# Copy_of_SCH_Placa_presentation.net
KiCad netlist of a schematic drawn in Altium Designer
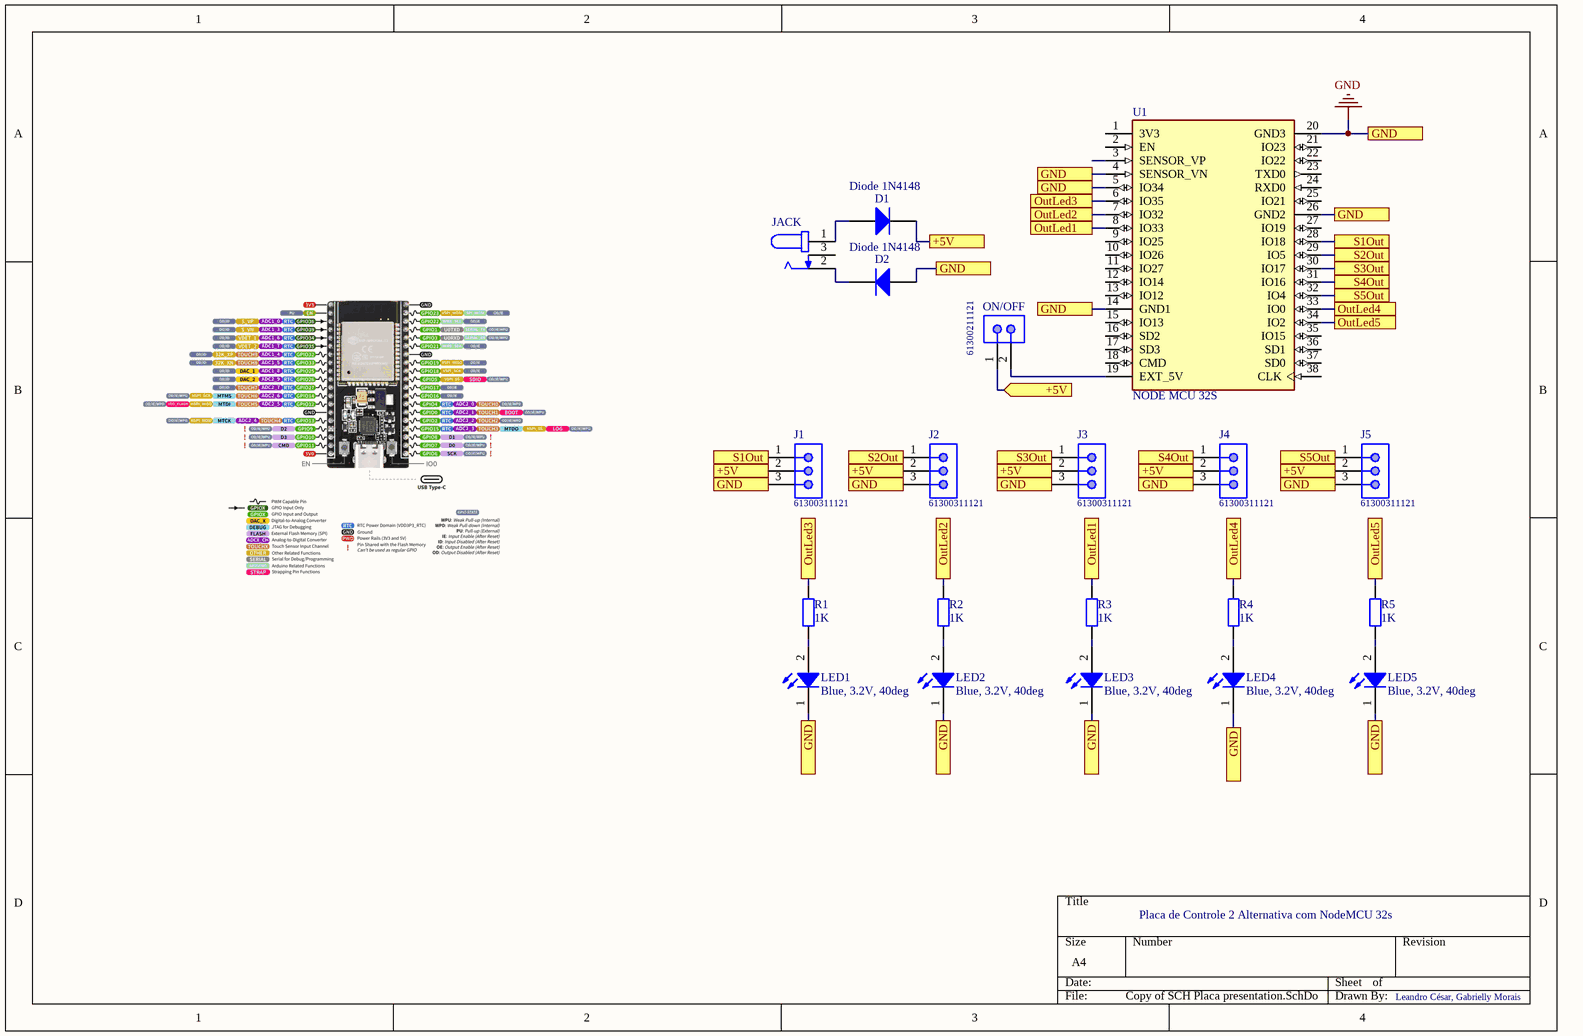
[diagram p0: Copy of SCH Placa presentation.SchDoc]

(export (version "E")
  (design (tool "Eeschema 10.0.6"))
  (components
    (comp (ref "D1")
      (value "Diode 1N4148")
      (footprint "DO-35")
      (description "High Conductance Fast Diode")
      (fields (field (name "PUBLISHER") "Altium Limited"))
      (libsource (lib "Biblioteca_Ex_Machina_v1.6.0") (part "Diode 1N4148"))
    )
    (comp (ref "D2")
      (value "Diode 1N4148")
      (footprint "DO-35")
      (description "High Conductance Fast Diode")
      (fields (field (name "PUBLISHER") "Altium Limited"))
      (libsource (lib "Biblioteca_Ex_Machina_v1.6.0") (part "Diode 1N4148"))
    )
    (comp (ref "J1")
      (value "61300311121")
      (footprint "61300311121")
      (description "WR-PHD Pin Header, THT, pitch 2.54mm, Single Row, Vertical, 3pin")
      (fields (field (name "PUBLISHER") "Wurth Elektronik"))
      (libsource (lib "Biblioteca_Ex_Machina_v1.6.0") (part "61300311121"))
    )
    (comp (ref "J2")
      (value "61300311121")
      (footprint "61300311121")
      (description "WR-PHD Pin Header, THT, pitch 2.54mm, Single Row, Vertical, 3pin")
      (fields (field (name "PUBLISHER") "Wurth Elektronik"))
      (libsource (lib "Biblioteca_Ex_Machina_v1.6.0") (part "61300311121"))
    )
    (comp (ref "J3")
      (value "61300311121")
      (footprint "61300311121")
      (description "WR-PHD Pin Header, THT, pitch 2.54mm, Single Row, Vertical, 3pin")
      (fields (field (name "PUBLISHER") "Wurth Elektronik"))
      (libsource (lib "Biblioteca_Ex_Machina_v1.6.0") (part "61300311121"))
    )
    (comp (ref "J4")
      (value "61300311121")
      (footprint "61300311121")
      (description "WR-PHD Pin Header, THT, pitch 2.54mm, Single Row, Vertical, 3pin")
      (fields (field (name "PUBLISHER") "Wurth Elektronik"))
      (libsource (lib "Biblioteca_Ex_Machina_v1.6.0") (part "61300311121"))
    )
    (comp (ref "J5")
      (value "61300311121")
      (footprint "61300311121")
      (description "WR-PHD Pin Header, THT, pitch 2.54mm, Single Row, Vertical, 3pin")
      (fields (field (name "PUBLISHER") "Wurth Elektronik"))
      (libsource (lib "Biblioteca_Ex_Machina_v1.6.0") (part "61300311121"))
    )
    (comp (ref "JACK")
      (value "DCJ200-10-A-XX-K_REVA")
      (footprint "GCT_DCJ200-10-A-XX-K_REVA")
      (description "Power Barrel Connector Jack 2.05mm ID (0.081), 5.50mm OD (0.217) Through Hole, Right Angle")
      (fields (field (name "MF") "Global Connector Technology") (field (name "MP") "DCJ200-10-A-K1-K"))
      (libsource (lib "DCJ200-10-A-XX-K_REVA (2)") (part "DCJ200-10-A-XX-K_REVA"))
    )
    (comp (ref "LED1")
      (value "Blue, 3.2V, 40deg")
      (footprint "LED RED 3MM")
      (description "LED WL-TMRC THT Mono-color Round")
      (fields (field (name "PART NUMBER") "151051BS04000") (field (name "PUBLISHER") "Wurth Elektronik"))
      (libsource (lib "Biblioteca_Ex_Machina_v1.6.0") (part "LED"))
    )
    (comp (ref "LED2")
      (value "Blue, 3.2V, 40deg")
      (footprint "LED RED 3MM")
      (description "LED WL-TMRC THT Mono-color Round")
      (fields (field (name "PART NUMBER") "151051BS04000") (field (name "PUBLISHER") "Wurth Elektronik"))
      (libsource (lib "Biblioteca_Ex_Machina_v1.6.0") (part "LED"))
    )
    (comp (ref "LED3")
      (value "Blue, 3.2V, 40deg")
      (footprint "LED RED 3MM")
      (description "LED WL-TMRC THT Mono-color Round")
      (fields (field (name "PART NUMBER") "151051BS04000") (field (name "PUBLISHER") "Wurth Elektronik"))
      (libsource (lib "Biblioteca_Ex_Machina_v1.6.0") (part "LED"))
    )
    (comp (ref "LED4")
      (value "Blue, 3.2V, 40deg")
      (footprint "LED RED 3MM")
      (description "LED WL-TMRC THT Mono-color Round")
      (fields (field (name "PART NUMBER") "151051BS04000") (field (name "PUBLISHER") "Wurth Elektronik"))
      (libsource (lib "Biblioteca_Ex_Machina_v1.6.0") (part "LED"))
    )
    (comp (ref "LED5")
      (value "Blue, 3.2V, 40deg")
      (footprint "LED RED 3MM")
      (description "LED WL-TMRC THT Mono-color Round")
      (fields (field (name "PART NUMBER") "151051BS04000") (field (name "PUBLISHER") "Wurth Elektronik"))
      (libsource (lib "Biblioteca_Ex_Machina_v1.6.0") (part "LED"))
    )
    (comp (ref "ON/OFF")
      (value "61300211121")
      (footprint "61300211121")
      (description "WR-PHD Pin Header, THT, pitch 2.54mm, Single Row, Vertical, 2pin")
      (fields (field (name "PUBLISHER") "Wurth Elektronik"))
      (libsource (lib "Biblioteca_Ex_Machina_v1.6.0") (part "61300211121"))
    )
    (comp (ref "R1")
      (value "1K")
      (footprint "RES AXIAL-0.4")
      (description "Resistor")
      (fields (field (name "Comment") "Res") (field (name "PUBLISHER") "Altium Limited"))
      (libsource (lib "Biblioteca_Ex_Machina_v1.6.0") (part "Res"))
    )
    (comp (ref "R2")
      (value "1K")
      (footprint "RES AXIAL-0.4")
      (description "Resistor")
      (fields (field (name "Comment") "Res") (field (name "PUBLISHER") "Altium Limited"))
      (libsource (lib "Biblioteca_Ex_Machina_v1.6.0") (part "Res"))
    )
    (comp (ref "R3")
      (value "1K")
      (footprint "RES AXIAL-0.4")
      (description "Resistor")
      (fields (field (name "Comment") "Res") (field (name "PUBLISHER") "Altium Limited"))
      (libsource (lib "Biblioteca_Ex_Machina_v1.6.0") (part "Res"))
    )
    (comp (ref "R4")
      (value "1K")
      (footprint "RES AXIAL-0.4")
      (description "Resistor")
      (fields (field (name "Comment") "Res") (field (name "PUBLISHER") "Altium Limited"))
      (libsource (lib "Biblioteca_Ex_Machina_v1.6.0") (part "Res"))
    )
    (comp (ref "R5")
      (value "1K")
      (footprint "RES AXIAL-0.4")
      (description "Resistor")
      (fields (field (name "Comment") "Res") (field (name "PUBLISHER") "Altium Limited"))
      (libsource (lib "Biblioteca_Ex_Machina_v1.6.0") (part "Res"))
    )
    (comp (ref "U1")
      (value "NODE MCU 32S")
      (footprint "BOARD")
      (fields (field (name "MP") "ESP32-DEVKITC-32D") (field (name "MF") "Espressif Systems"))
      (libsource (lib "Biblioteca_Ex_Machina_v1.6.0") (part "NODE MCU 32S"))
    )
  )
  (nets
    (net (code "1") (name "/+5V") (class "Default")
      (node (ref "D1") (pin "2") (pinfunction "K_2") (pintype "passive"))
      (node (ref "J1") (pin "2") (pinfunction "2_2") (pintype "passive"))
      (node (ref "J2") (pin "2") (pinfunction "2_2") (pintype "passive"))
      (node (ref "J3") (pin "2") (pinfunction "2_2") (pintype "passive"))
      (node (ref "J4") (pin "2") (pinfunction "2_2") (pintype "passive"))
      (node (ref "J5") (pin "2") (pinfunction "2_2") (pintype "passive"))
      (node (ref "ON/OFF") (pin "1") (pinfunction "1_1") (pintype "passive"))
    )
    (net (code "2") (name "/OutLed1") (class "Default")
      (node (ref "R3") (pin "1") (pinfunction "1_1") (pintype "passive"))
      (node (ref "U1") (pin "8") (pinfunction "IO33_8") (pintype "bidirectional"))
    )
    (net (code "3") (name "/OutLed2") (class "Default")
      (node (ref "R2") (pin "1") (pinfunction "1_1") (pintype "passive"))
      (node (ref "U1") (pin "7") (pinfunction "IO32_7") (pintype "bidirectional"))
    )
    (net (code "4") (name "/OutLed3") (class "Default")
      (node (ref "R1") (pin "1") (pinfunction "1_1") (pintype "passive"))
      (node (ref "U1") (pin "6") (pinfunction "IO35_6") (pintype "bidirectional"))
    )
    (net (code "5") (name "/OutLed4") (class "Default")
      (node (ref "R4") (pin "1") (pinfunction "1_1") (pintype "passive"))
      (node (ref "U1") (pin "33") (pinfunction "IO0_33") (pintype "bidirectional"))
    )
    (net (code "6") (name "/OutLed5") (class "Default")
      (node (ref "R5") (pin "1") (pinfunction "1_1") (pintype "passive"))
      (node (ref "U1") (pin "34") (pinfunction "IO2_34") (pintype "bidirectional"))
    )
    (net (code "7") (name "/S1Out") (class "Default")
      (node (ref "J1") (pin "1") (pinfunction "1_1") (pintype "passive"))
      (node (ref "U1") (pin "28") (pinfunction "IO18_28") (pintype "bidirectional"))
    )
    (net (code "8") (name "/S2Out") (class "Default")
      (node (ref "J2") (pin "1") (pinfunction "1_1") (pintype "passive"))
      (node (ref "U1") (pin "29") (pinfunction "IO5_29") (pintype "bidirectional"))
    )
    (net (code "9") (name "/S3Out") (class "Default")
      (node (ref "J3") (pin "1") (pinfunction "1_1") (pintype "passive"))
      (node (ref "U1") (pin "30") (pinfunction "IO17_30") (pintype "bidirectional"))
    )
    (net (code "10") (name "/S4Out") (class "Default")
      (node (ref "J4") (pin "1") (pinfunction "1_1") (pintype "passive"))
      (node (ref "U1") (pin "31") (pinfunction "IO16_31") (pintype "bidirectional"))
    )
    (net (code "11") (name "/S5Out") (class "Default")
      (node (ref "J5") (pin "1") (pinfunction "1_1") (pintype "passive"))
      (node (ref "U1") (pin "32") (pinfunction "IO4_32") (pintype "bidirectional"))
    )
    (net (code "12") (name "GND") (class "Default")
      (node (ref "D2") (pin "1") (pinfunction "A_1") (pintype "passive"))
      (node (ref "J1") (pin "3") (pinfunction "3_3") (pintype "passive"))
      (node (ref "J2") (pin "3") (pinfunction "3_3") (pintype "passive"))
      (node (ref "J3") (pin "3") (pinfunction "3_3") (pintype "passive"))
      (node (ref "J4") (pin "3") (pinfunction "3_3") (pintype "passive"))
      (node (ref "J5") (pin "3") (pinfunction "3_3") (pintype "passive"))
      (node (ref "LED1") (pin "1") (pinfunction "K_1") (pintype "passive"))
      (node (ref "LED2") (pin "1") (pinfunction "K_1") (pintype "passive"))
      (node (ref "LED3") (pin "1") (pinfunction "K_1") (pintype "passive"))
      (node (ref "LED4") (pin "1") (pinfunction "K_1") (pintype "passive"))
      (node (ref "LED5") (pin "1") (pinfunction "K_1") (pintype "passive"))
      (node (ref "U1") (pin "14") (pinfunction "GND1_14") (pintype "power_in"))
      (node (ref "U1") (pin "20") (pinfunction "GND3_20") (pintype "power_in"))
      (node (ref "U1") (pin "26") (pinfunction "GND2_26") (pintype "power_in"))
      (node (ref "U1") (pin "4") (pinfunction "SENSOR_VN_4") (pintype "input"))
      (node (ref "U1") (pin "5") (pinfunction "IO34_5") (pintype "bidirectional"))
    )
    (net (code "13") (name "Net-(D1-A)") (class "Default")
      (node (ref "D1") (pin "1") (pinfunction "A_1") (pintype "passive"))
      (node (ref "JACK") (pin "1") (pinfunction "1_1") (pintype "passive"))
    )
    (net (code "14") (name "Net-(D2-K)") (class "Default")
      (node (ref "D2") (pin "2") (pinfunction "K_2") (pintype "passive"))
      (node (ref "JACK") (pin "2") (pinfunction "2_2") (pintype "passive"))
    )
    (net (code "15") (name "Net-(LED1-A)") (class "Default")
      (node (ref "LED1") (pin "2") (pinfunction "A_2") (pintype "passive"))
      (node (ref "R1") (pin "2") (pinfunction "2_2") (pintype "passive"))
    )
    (net (code "16") (name "Net-(LED2-A)") (class "Default")
      (node (ref "LED2") (pin "2") (pinfunction "A_2") (pintype "passive"))
      (node (ref "R2") (pin "2") (pinfunction "2_2") (pintype "passive"))
    )
    (net (code "17") (name "Net-(LED3-A)") (class "Default")
      (node (ref "LED3") (pin "2") (pinfunction "A_2") (pintype "passive"))
      (node (ref "R3") (pin "2") (pinfunction "2_2") (pintype "passive"))
    )
    (net (code "18") (name "Net-(LED4-A)") (class "Default")
      (node (ref "LED4") (pin "2") (pinfunction "A_2") (pintype "passive"))
      (node (ref "R4") (pin "2") (pinfunction "2_2") (pintype "passive"))
    )
    (net (code "19") (name "Net-(LED5-A)") (class "Default")
      (node (ref "LED5") (pin "2") (pinfunction "A_2") (pintype "passive"))
      (node (ref "R5") (pin "2") (pinfunction "2_2") (pintype "passive"))
    )
    (net (code "20") (name "Net-(U1-EXT_5V)") (class "Default")
      (node (ref "ON/OFF") (pin "2") (pinfunction "2_2") (pintype "passive"))
      (node (ref "U1") (pin "19") (pinfunction "EXT_5V_19") (pintype "power_in"))
    )
    (net (code "21") (name "unconnected-(JACK-Pad3)") (class "Default")
      (node (ref "JACK") (pin "3") (pinfunction "3_3") (pintype "passive"))
    )
    (net (code "22") (name "unconnected-(U1-3V3-Pad1)") (class "Default")
      (node (ref "U1") (pin "1") (pinfunction "3V3_1") (pintype "power_in"))
    )
    (net (code "23") (name "unconnected-(U1-CLK-Pad38)") (class "Default")
      (node (ref "U1") (pin "38") (pinfunction "CLK_38") (pintype "input"))
    )
    (net (code "24") (name "unconnected-(U1-CMD-Pad18)") (class "Default")
      (node (ref "U1") (pin "18") (pinfunction "CMD_18") (pintype "bidirectional"))
    )
    (net (code "25") (name "unconnected-(U1-EN-Pad2)") (class "Default")
      (node (ref "U1") (pin "2") (pinfunction "EN_2") (pintype "input"))
    )
    (net (code "26") (name "unconnected-(U1-IO12-Pad13)") (class "Default")
      (node (ref "U1") (pin "13") (pinfunction "IO12_13") (pintype "bidirectional"))
    )
    (net (code "27") (name "unconnected-(U1-IO13-Pad15)") (class "Default")
      (node (ref "U1") (pin "15") (pinfunction "IO13_15") (pintype "bidirectional"))
    )
    (net (code "28") (name "unconnected-(U1-IO14-Pad12)") (class "Default")
      (node (ref "U1") (pin "12") (pinfunction "IO14_12") (pintype "bidirectional"))
    )
    (net (code "29") (name "unconnected-(U1-IO15-Pad35)") (class "Default")
      (node (ref "U1") (pin "35") (pinfunction "IO15_35") (pintype "bidirectional"))
    )
    (net (code "30") (name "unconnected-(U1-IO19-Pad27)") (class "Default")
      (node (ref "U1") (pin "27") (pinfunction "IO19_27") (pintype "bidirectional"))
    )
    (net (code "31") (name "unconnected-(U1-IO21-Pad25)") (class "Default")
      (node (ref "U1") (pin "25") (pinfunction "IO21_25") (pintype "bidirectional"))
    )
    (net (code "32") (name "unconnected-(U1-IO22-Pad22)") (class "Default")
      (node (ref "U1") (pin "22") (pinfunction "IO22_22") (pintype "bidirectional"))
    )
    (net (code "33") (name "unconnected-(U1-IO23-Pad21)") (class "Default")
      (node (ref "U1") (pin "21") (pinfunction "IO23_21") (pintype "bidirectional"))
    )
    (net (code "34") (name "unconnected-(U1-IO25-Pad9)") (class "Default")
      (node (ref "U1") (pin "9") (pinfunction "IO25_9") (pintype "bidirectional"))
    )
    (net (code "35") (name "unconnected-(U1-IO26-Pad10)") (class "Default")
      (node (ref "U1") (pin "10") (pinfunction "IO26_10") (pintype "bidirectional"))
    )
    (net (code "36") (name "unconnected-(U1-IO27-Pad11)") (class "Default")
      (node (ref "U1") (pin "11") (pinfunction "IO27_11") (pintype "bidirectional"))
    )
    (net (code "37") (name "unconnected-(U1-RXD0-Pad24)") (class "Default")
      (node (ref "U1") (pin "24") (pinfunction "RXD0_24") (pintype "input"))
    )
    (net (code "38") (name "unconnected-(U1-SD0-Pad37)") (class "Default")
      (node (ref "U1") (pin "37") (pinfunction "SD0_37") (pintype "bidirectional"))
    )
    (net (code "39") (name "unconnected-(U1-SD1-Pad36)") (class "Default")
      (node (ref "U1") (pin "36") (pinfunction "SD1_36") (pintype "bidirectional"))
    )
    (net (code "40") (name "unconnected-(U1-SD2-Pad16)") (class "Default")
      (node (ref "U1") (pin "16") (pinfunction "SD2_16") (pintype "bidirectional"))
    )
    (net (code "41") (name "unconnected-(U1-SD3-Pad17)") (class "Default")
      (node (ref "U1") (pin "17") (pinfunction "SD3_17") (pintype "bidirectional"))
    )
    (net (code "42") (name "unconnected-(U1-SENSOR_VP-Pad3)") (class "Default")
      (node (ref "U1") (pin "3") (pinfunction "SENSOR_VP_3") (pintype "input"))
    )
    (net (code "43") (name "unconnected-(U1-TXD0-Pad23)") (class "Default")
      (node (ref "U1") (pin "23") (pinfunction "TXD0_23") (pintype "output"))
    )
  )
)
